# PCI_Express.net
KiCad netlist of a schematic drawn in Altium Designer
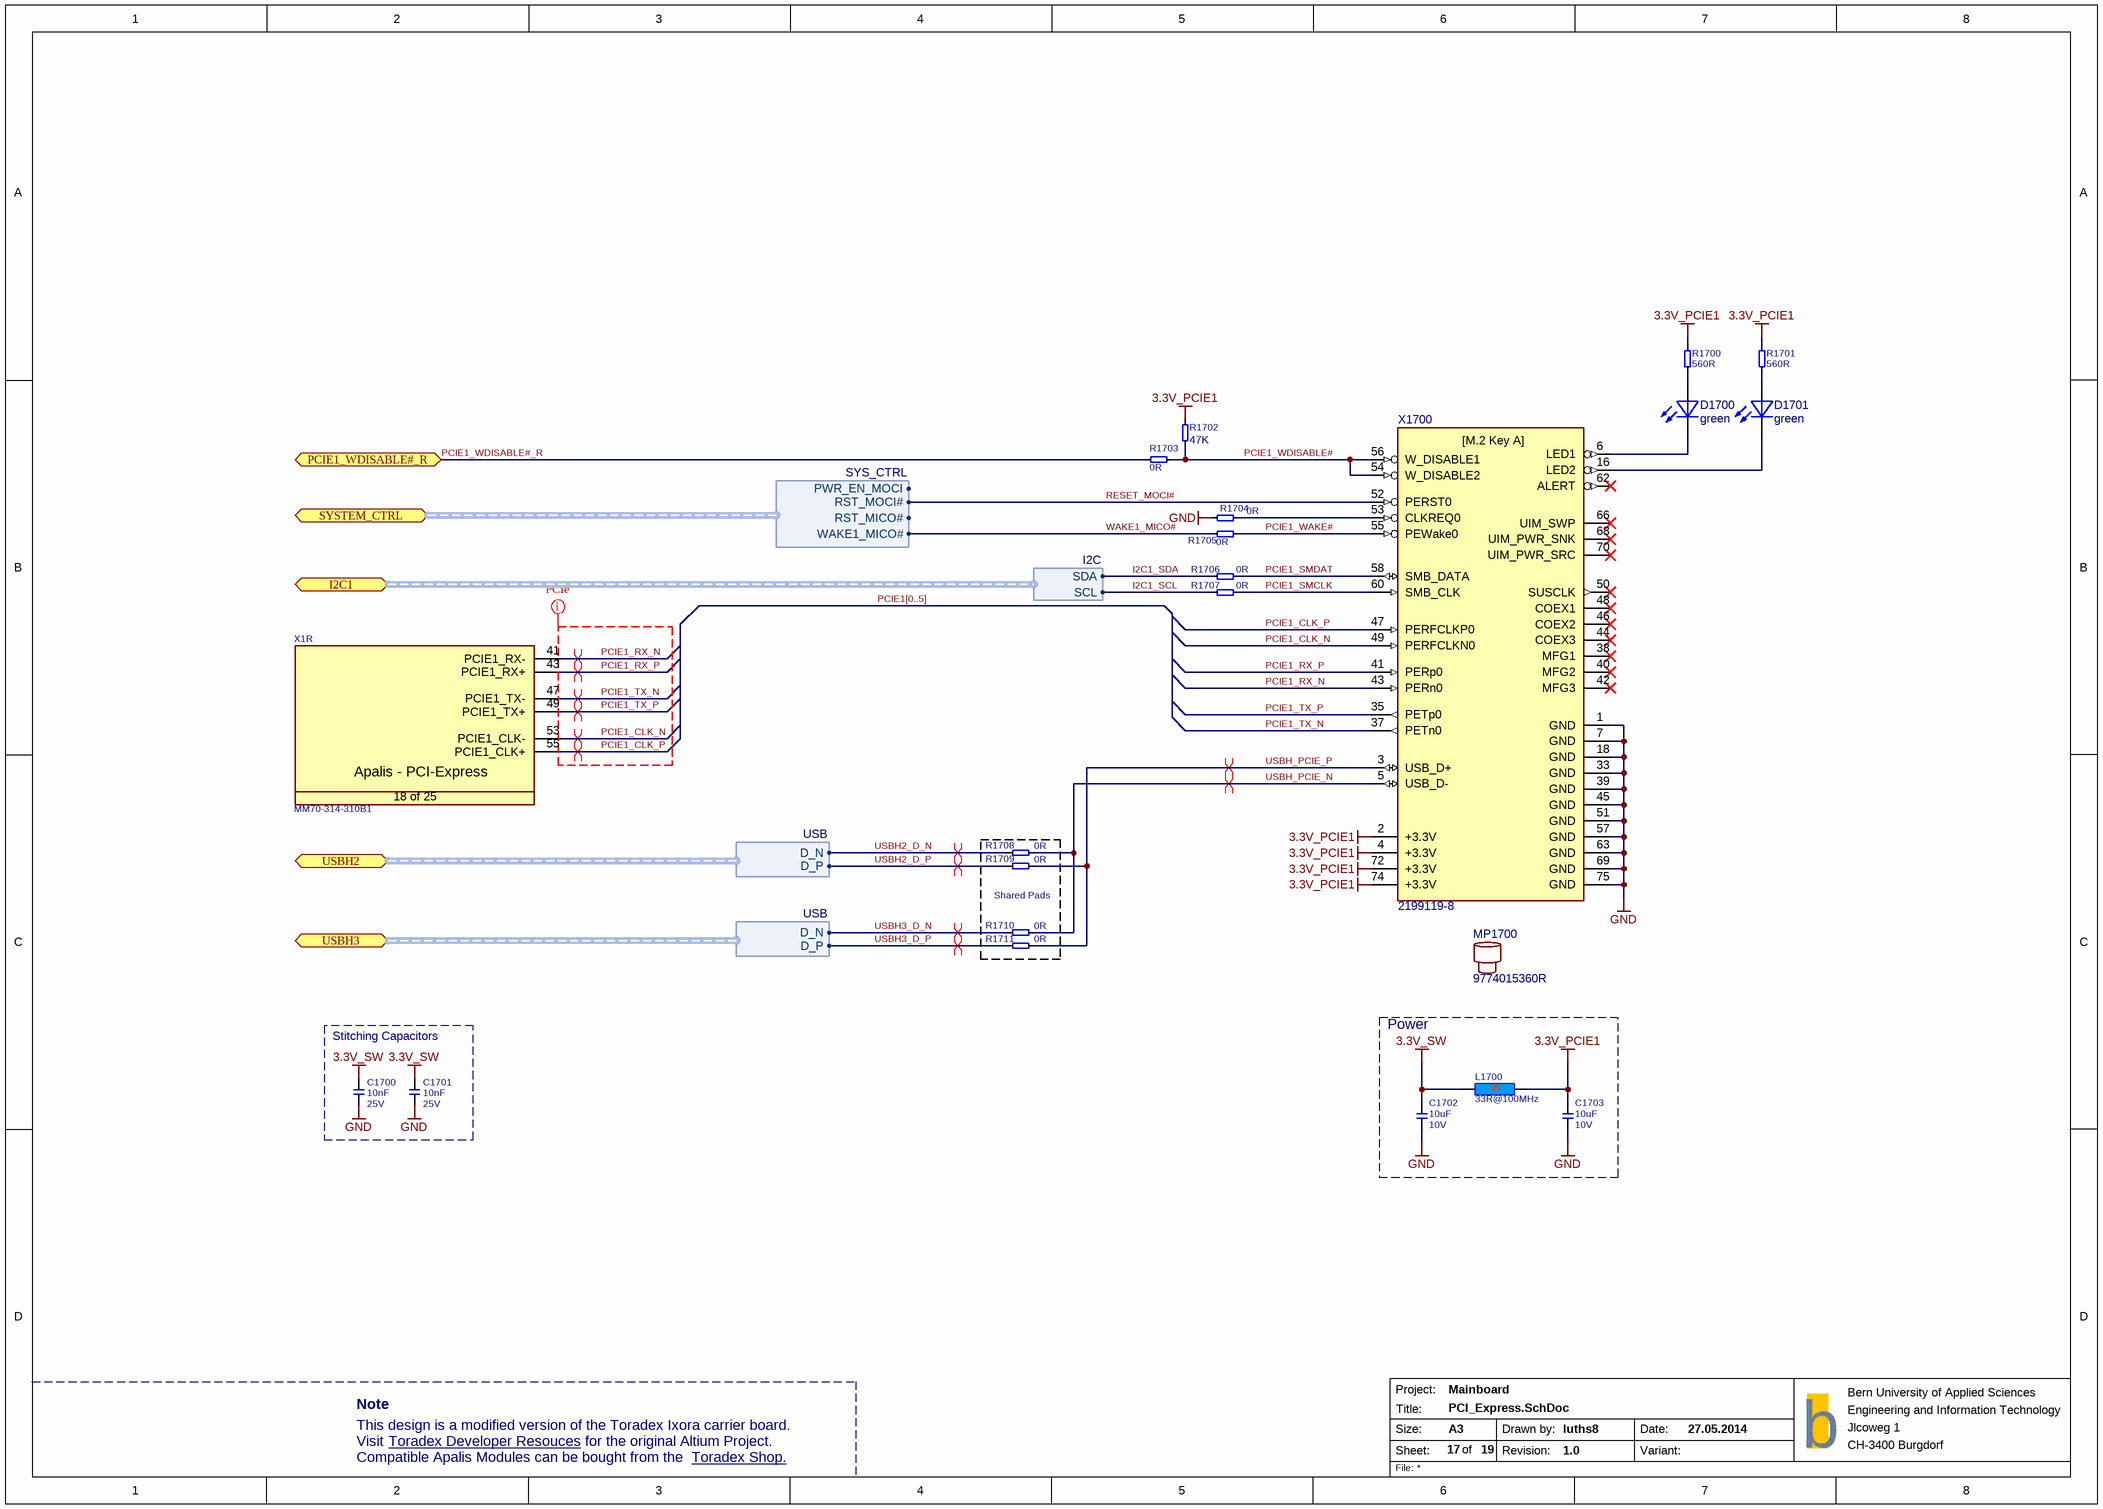
[diagram p0: PCI_Express.SchDoc]

(export (version "E")
  (design (tool "Eeschema 10.0.6"))
  (components
    (comp (ref "C1700")
      (value "10nF")
      (footprint "SMD0603CAP")
      (description "Capacitor Ceramic X7R 10nF 25V 10% 0603")
      (fields (field (name "TOLERANCE") "10%") (field (name "RATING") "25V"))
      (libsource (lib "Ixora") (part "C-X7R-10nF-25V-10%-0603"))
    )
    (comp (ref "C1701")
      (value "10nF")
      (footprint "SMD0603CAP")
      (description "Capacitor Ceramic X7R 10nF 25V 10% 0603")
      (fields (field (name "TOLERANCE") "10%") (field (name "RATING") "25V"))
      (libsource (lib "Ixora") (part "C-X7R-10nF-25V-10%-0603"))
    )
    (comp (ref "C1702")
      (value "10uF")
      (footprint "SMD0603CAP")
      (description "Capacitor Ceramic X5R 10uF 10V 20% 0603")
      (fields (field (name "TOLERANCE") "20%") (field (name "RATING") "10V"))
      (libsource (lib "Ixora") (part "C-X5R-10uF-10V-20%-0603"))
    )
    (comp (ref "C1703")
      (value "10uF")
      (footprint "SMD0603CAP")
      (description "Capacitor Ceramic X5R 10uF 10V 20% 0603")
      (fields (field (name "TOLERANCE") "20%") (field (name "RATING") "10V"))
      (libsource (lib "Ixora") (part "C-X5R-10uF-10V-20%-0603"))
    )
    (comp (ref "D1700")
      (value "green")
      (footprint "LED")
      (description "LED green")
      (fields (field (name "MANUFACTURER PART NO.") "LGM67KG1J224Z"))
      (libsource (lib "Audio-Streamer") (part "LED green"))
    )
    (comp (ref "D1701")
      (value "green")
      (footprint "LED")
      (description "LED green")
      (fields (field (name "MANUFACTURER PART NO.") "LGM67KG1J224Z"))
      (libsource (lib "Audio-Streamer") (part "LED green"))
    )
    (comp (ref "L1700")
      (value "33R@100MHz")
      (footprint "INDC1608X95N")
      (description "33R@100MHz 3A EMI FILTER")
      (fields (field (name "TOLERANCE") "25%"))
      (libsource (lib "Ixora") (part "L-33R@100MHz-3A-25%-0603"))
    )
    (comp (ref "MP1700")
      (value "9774015360R")
      (description "Spacer M3 SMD")
      (libsource (lib "Audio-Streamer") (part "Spacer M3 SMD"))
    )
    (comp (ref "R1700")
      (value "560R")
      (footprint "SMD0603RES")
      (description "Resistor 560 ohm 63mW 5% 0603")
      (fields (field (name "TOLERANCE") "5%"))
      (libsource (lib "Ixora") (part "R-560R-63mW-5%-0402"))
    )
    (comp (ref "R1701")
      (value "560R")
      (footprint "SMD0603RES")
      (description "Resistor 560 ohm 63mW 5% 0603")
      (fields (field (name "TOLERANCE") "5%"))
      (libsource (lib "Ixora") (part "R-560R-63mW-5%-0402"))
    )
    (comp (ref "R1702")
      (value "47K")
      (footprint "SMD0603RES")
      (description "Resistor 47 Kohm 63mW 5% 0603")
      (fields (field (name "TOLERANCE") "5%"))
      (libsource (lib "Ixora") (part "R-47KR-63mW-5%-0603"))
    )
    (comp (ref "R1703")
      (value "0R")
      (footprint "SMD0603RES")
      (description "Resistor 0 ohm 63mW 1% 0603")
      (fields (field (name "TOLERANCE") "1%"))
      (libsource (lib "Ixora") (part "R-0R-63mW-1%-0603"))
    )
    (comp (ref "R1704")
      (value "0R")
      (footprint "SMD0603RES")
      (description "Resistor 0 ohm 63mW 1% 0603")
      (fields (field (name "TOLERANCE") "1%"))
      (libsource (lib "Ixora") (part "R-0R-63mW-1%-0603"))
    )
    (comp (ref "R1705")
      (value "0R")
      (footprint "SMD0603RES")
      (description "Resistor 0 ohm 63mW 1% 0603")
      (fields (field (name "TOLERANCE") "1%"))
      (libsource (lib "Ixora") (part "R-0R-63mW-1%-0603"))
    )
    (comp (ref "R1706")
      (value "0R")
      (footprint "SMD0603RES")
      (description "Resistor 0 ohm 63mW 1% 0603")
      (fields (field (name "TOLERANCE") "1%"))
      (libsource (lib "Ixora") (part "R-0R-63mW-1%-0402"))
    )
    (comp (ref "R1707")
      (value "0R")
      (footprint "SMD0603RES")
      (description "Resistor 0 ohm 63mW 1% 0603")
      (fields (field (name "TOLERANCE") "1%"))
      (libsource (lib "Ixora") (part "R-0R-63mW-1%-0402"))
    )
    (comp (ref "R1708")
      (value "0R")
      (footprint "SMD0603RES")
      (description "Resistor 0 ohm 63mW 1% 0603")
      (fields (field (name "TOLERANCE") "1%"))
      (libsource (lib "Ixora") (part "R-0R-63mW-1%-0603"))
    )
    (comp (ref "R1709")
      (value "0R")
      (footprint "SMD0603RES")
      (description "Resistor 0 ohm 63mW 1% 0603")
      (fields (field (name "TOLERANCE") "1%"))
      (libsource (lib "Ixora") (part "R-0R-63mW-1%-0603"))
    )
    (comp (ref "R1710")
      (value "0R")
      (footprint "SMD0603RES")
      (description "Resistor 0 ohm 63mW 1% 0603")
      (fields (field (name "TOLERANCE") "1%"))
      (libsource (lib "Ixora") (part "R-0R-63mW-1%-0603"))
    )
    (comp (ref "R1711")
      (value "0R")
      (footprint "SMD0603RES")
      (description "Resistor 0 ohm 63mW 1% 0603")
      (fields (field (name "TOLERANCE") "1%"))
      (libsource (lib "Ixora") (part "R-0R-63mW-1%-0603"))
    )
    (comp (ref "X1")
      (value "CON-JAE-MM70-314-310B1-314-0.5mm")
      (footprint "T_JAE_MM70-314-310B1")
      (description "MXM3 Connector")
      (fields (field (name "MANUFACTURER PART NO.") "MM70-314-310B1"))
      (libsource (lib "Ixora") (part "CON-JAE-MM70-314-310B1-314-0.5mm"))
    )
    (comp (ref "X1700")
      (value "2199119-8")
      (footprint "2199119-8-KEY-A-2230")
      (description "Connector M.2 Key A")
      (libsource (lib "Audio-Streamer") (part "Connector M.2 Key A"))
    )
  )
  (nets
    (net (code "10") (name "/I2C1_SCL") (class "Default")
      (node (ref "R1707") (pin "1") (pinfunction "1_1") (pintype "passive"))
    )
    (net (code "11") (name "/I2C1_SDA") (class "Default")
      (node (ref "R1706") (pin "1") (pinfunction "1_1") (pintype "passive"))
    )
    (net (code "13") (name "/PCIE1_CLK_N") (class "Default")
      (node (ref "X1") (pin "53") (pinfunction "PCIE1_CLK-_53") (pintype "passive"))
      (node (ref "X1700") (pin "49") (pinfunction "PERFCLKN0_49") (pintype "input"))
    )
    (net (code "14") (name "/PCIE1_CLK_P") (class "Default")
      (node (ref "X1") (pin "55") (pinfunction "PCIE1_CLK+_55") (pintype "passive"))
      (node (ref "X1700") (pin "47") (pinfunction "PERFCLKP0_47") (pintype "input"))
    )
    (net (code "15") (name "/PCIE1_RX_N") (class "Default")
      (node (ref "X1") (pin "41") (pinfunction "PCIE1_RX-_41") (pintype "passive"))
      (node (ref "X1700") (pin "43") (pinfunction "PERn0_43") (pintype "input"))
    )
    (net (code "16") (name "/PCIE1_RX_P") (class "Default")
      (node (ref "X1") (pin "43") (pinfunction "PCIE1_RX+_43") (pintype "passive"))
      (node (ref "X1700") (pin "41") (pinfunction "PERp0_41") (pintype "input"))
    )
    (net (code "17") (name "/PCIE1_SMCLK") (class "Default")
      (node (ref "R1707") (pin "2") (pinfunction "2_2") (pintype "passive"))
      (node (ref "X1700") (pin "60") (pinfunction "SMB_CLK_60") (pintype "input"))
    )
    (net (code "18") (name "/PCIE1_SMDAT") (class "Default")
      (node (ref "R1706") (pin "2") (pinfunction "2_2") (pintype "passive"))
      (node (ref "X1700") (pin "58") (pinfunction "SMB_DATA_58") (pintype "bidirectional"))
    )
    (net (code "19") (name "/PCIE1_TX_N") (class "Default")
      (node (ref "X1") (pin "47") (pinfunction "PCIE1_TX-_47") (pintype "passive"))
      (node (ref "X1700") (pin "37") (pinfunction "PETn0_37") (pintype "output"))
    )
    (net (code "20") (name "/PCIE1_TX_P") (class "Default")
      (node (ref "X1") (pin "49") (pinfunction "PCIE1_TX+_49") (pintype "passive"))
      (node (ref "X1700") (pin "35") (pinfunction "PETp0_35") (pintype "output"))
    )
    (net (code "21") (name "/PCIE1_WAKE#") (class "Default")
      (node (ref "R1705") (pin "2") (pinfunction "2_2") (pintype "passive"))
      (node (ref "X1700") (pin "55") (pinfunction "PEWake0_55") (pintype "input"))
    )
    (net (code "22") (name "/PCIE1_WDISABLE#") (class "Default")
      (node (ref "R1702") (pin "1") (pinfunction "1_1") (pintype "passive"))
      (node (ref "R1703") (pin "1") (pinfunction "1_1") (pintype "passive"))
      (node (ref "X1700") (pin "54") (pinfunction "W_DISABLE2_54") (pintype "input"))
      (node (ref "X1700") (pin "56") (pinfunction "W_DISABLE1_56") (pintype "input"))
    )
    (net (code "23") (name "/PCIE1_WDISABLE#_R") (class "Default")
      (node (ref "R1703") (pin "2") (pinfunction "2_2") (pintype "passive"))
    )
    (net (code "24") (name "/RESET_MOCI#") (class "Default")
      (node (ref "X1700") (pin "52") (pinfunction "PERST0_52") (pintype "input"))
    )
    (net (code "27") (name "/USBH3_D_N") (class "Default")
      (node (ref "R1710") (pin "1") (pinfunction "1_1") (pintype "passive"))
    )
    (net (code "28") (name "/USBH3_D_P") (class "Default")
      (node (ref "R1711") (pin "1") (pinfunction "1_1") (pintype "passive"))
    )
    (net (code "29") (name "/USBH_PCIE_N") (class "Default")
      (node (ref "R1708") (pin "2") (pinfunction "2_2") (pintype "passive"))
      (node (ref "R1710") (pin "2") (pinfunction "2_2") (pintype "passive"))
      (node (ref "X1700") (pin "5") (pinfunction "USB_D-_5") (pintype "bidirectional"))
    )
    (net (code "30") (name "/USBH_PCIE_P") (class "Default")
      (node (ref "R1709") (pin "2") (pinfunction "2_2") (pintype "passive"))
      (node (ref "R1711") (pin "2") (pinfunction "2_2") (pintype "passive"))
      (node (ref "X1700") (pin "3") (pinfunction "USB_D+_3") (pintype "bidirectional"))
    )
    (net (code "31") (name "/WAKE1_MICO#") (class "Default")
      (node (ref "R1705") (pin "1") (pinfunction "1_1") (pintype "passive"))
    )
    (net (code "35") (name "3.3V_PCIE1") (class "Default")
      (node (ref "C1703") (pin "2") (pinfunction "2_2") (pintype "passive"))
      (node (ref "L1700") (pin "2") (pinfunction "2_2") (pintype "passive"))
      (node (ref "R1700") (pin "1") (pinfunction "1_1") (pintype "passive"))
      (node (ref "R1701") (pin "1") (pinfunction "1_1") (pintype "passive"))
      (node (ref "R1702") (pin "2") (pinfunction "2_2") (pintype "passive"))
      (node (ref "X1700") (pin "2") (pinfunction "+3.3V_2") (pintype "power_in"))
      (node (ref "X1700") (pin "4") (pinfunction "+3.3V_4") (pintype "power_in"))
      (node (ref "X1700") (pin "72") (pinfunction "+3.3V_72") (pintype "power_in"))
      (node (ref "X1700") (pin "74") (pinfunction "+3.3V_74") (pintype "power_in"))
    )
    (net (code "36") (name "3.3V_SW") (class "Default")
      (node (ref "C1700") (pin "2") (pinfunction "2_2") (pintype "passive"))
      (node (ref "C1701") (pin "2") (pinfunction "2_2") (pintype "passive"))
      (node (ref "C1702") (pin "2") (pinfunction "2_2") (pintype "passive"))
      (node (ref "L1700") (pin "1") (pinfunction "1_1") (pintype "passive"))
    )
    (net (code "37") (name "GND") (class "Default")
      (node (ref "C1700") (pin "1") (pinfunction "1_1") (pintype "passive"))
      (node (ref "C1701") (pin "1") (pinfunction "1_1") (pintype "passive"))
      (node (ref "C1702") (pin "1") (pinfunction "1_1") (pintype "passive"))
      (node (ref "C1703") (pin "1") (pinfunction "1_1") (pintype "passive"))
      (node (ref "R1704") (pin "1") (pinfunction "1_1") (pintype "passive"))
      (node (ref "X1700") (pin "1") (pinfunction "GND_1") (pintype "power_in"))
      (node (ref "X1700") (pin "18") (pinfunction "GND_18") (pintype "power_in"))
      (node (ref "X1700") (pin "33") (pinfunction "GND_33") (pintype "power_in"))
      (node (ref "X1700") (pin "39") (pinfunction "GND_39") (pintype "power_in"))
      (node (ref "X1700") (pin "45") (pinfunction "GND_45") (pintype "power_in"))
      (node (ref "X1700") (pin "51") (pinfunction "GND_51") (pintype "power_in"))
      (node (ref "X1700") (pin "57") (pinfunction "GND_57") (pintype "power_in"))
      (node (ref "X1700") (pin "63") (pinfunction "GND_63") (pintype "power_in"))
      (node (ref "X1700") (pin "69") (pinfunction "GND_69") (pintype "power_in"))
      (node (ref "X1700") (pin "7") (pinfunction "GND_7") (pintype "power_in"))
      (node (ref "X1700") (pin "75") (pinfunction "GND_75") (pintype "power_in"))
    )
    (net (code "38") (name "Net-(D1700-PadA)") (class "Default")
      (node (ref "D1700") (pin "A") (pinfunction "A_A") (pintype "passive"))
      (node (ref "R1700") (pin "2") (pinfunction "2_2") (pintype "passive"))
    )
    (net (code "39") (name "Net-(D1701-PadA)") (class "Default")
      (node (ref "D1701") (pin "A") (pinfunction "A_A") (pintype "passive"))
      (node (ref "R1701") (pin "2") (pinfunction "2_2") (pintype "passive"))
    )
    (net (code "40") (name "Net-(X1700-CLKREQ0)") (class "Default")
      (node (ref "R1704") (pin "2") (pinfunction "2_2") (pintype "passive"))
      (node (ref "X1700") (pin "53") (pinfunction "CLKREQ0_53") (pintype "input"))
    )
    (net (code "41") (name "Net-(X1700-LED1)") (class "Default")
      (node (ref "D1700") (pin "C") (pinfunction "C_C") (pintype "passive"))
      (node (ref "X1700") (pin "6") (pinfunction "LED1_6") (pintype "output"))
    )
    (net (code "42") (name "Net-(X1700-LED2)") (class "Default")
      (node (ref "D1701") (pin "C") (pinfunction "C_C") (pintype "passive"))
      (node (ref "X1700") (pin "16") (pinfunction "LED2_16") (pintype "output"))
    )
    (net (code "43") (name "unconnected-(R1708-Pad1)") (class "Default")
      (node (ref "R1708") (pin "1") (pinfunction "1_1") (pintype "passive"))
    )
    (net (code "44") (name "unconnected-(R1709-Pad1)") (class "Default")
      (node (ref "R1709") (pin "1") (pinfunction "1_1") (pintype "passive"))
    )
    (net (code "45") (name "unconnected-(X1700-ALERT-Pad62)") (class "Default")
      (node (ref "X1700") (pin "62") (pinfunction "ALERT_62") (pintype "output+no_connect"))
    )
    (net (code "46") (name "unconnected-(X1700-COEX1-Pad48)") (class "Default")
      (node (ref "X1700") (pin "48") (pinfunction "COEX1_48") (pintype "passive+no_connect"))
    )
    (net (code "47") (name "unconnected-(X1700-COEX2-Pad46)") (class "Default")
      (node (ref "X1700") (pin "46") (pinfunction "COEX2_46") (pintype "passive+no_connect"))
    )
    (net (code "48") (name "unconnected-(X1700-COEX3-Pad44)") (class "Default")
      (node (ref "X1700") (pin "44") (pinfunction "COEX3_44") (pintype "passive+no_connect"))
    )
    (net (code "49") (name "unconnected-(X1700-MFG1-Pad38)") (class "Default")
      (node (ref "X1700") (pin "38") (pinfunction "MFG1_38") (pintype "passive+no_connect"))
    )
    (net (code "50") (name "unconnected-(X1700-MFG2-Pad40)") (class "Default")
      (node (ref "X1700") (pin "40") (pinfunction "MFG2_40") (pintype "passive+no_connect"))
    )
    (net (code "51") (name "unconnected-(X1700-MFG3-Pad42)") (class "Default")
      (node (ref "X1700") (pin "42") (pinfunction "MFG3_42") (pintype "passive+no_connect"))
    )
    (net (code "52") (name "unconnected-(X1700-SUSCLK-Pad50)") (class "Default")
      (node (ref "X1700") (pin "50") (pinfunction "SUSCLK_50") (pintype "output+no_connect"))
    )
    (net (code "53") (name "unconnected-(X1700-UIM_PWR_SNK-Pad68)") (class "Default")
      (node (ref "X1700") (pin "68") (pinfunction "UIM_PWR_SNK_68") (pintype "passive+no_connect"))
    )
    (net (code "54") (name "unconnected-(X1700-UIM_PWR_SRC-Pad70)") (class "Default")
      (node (ref "X1700") (pin "70") (pinfunction "UIM_PWR_SRC_70") (pintype "passive+no_connect"))
    )
    (net (code "55") (name "unconnected-(X1700-UIM_SWP-Pad66)") (class "Default")
      (node (ref "X1700") (pin "66") (pinfunction "UIM_SWP_66") (pintype "passive+no_connect"))
    )
  )
)
